# cpb-dslr-remote-shield.net
KiCad netlist of a schematic drawn in EAGLE
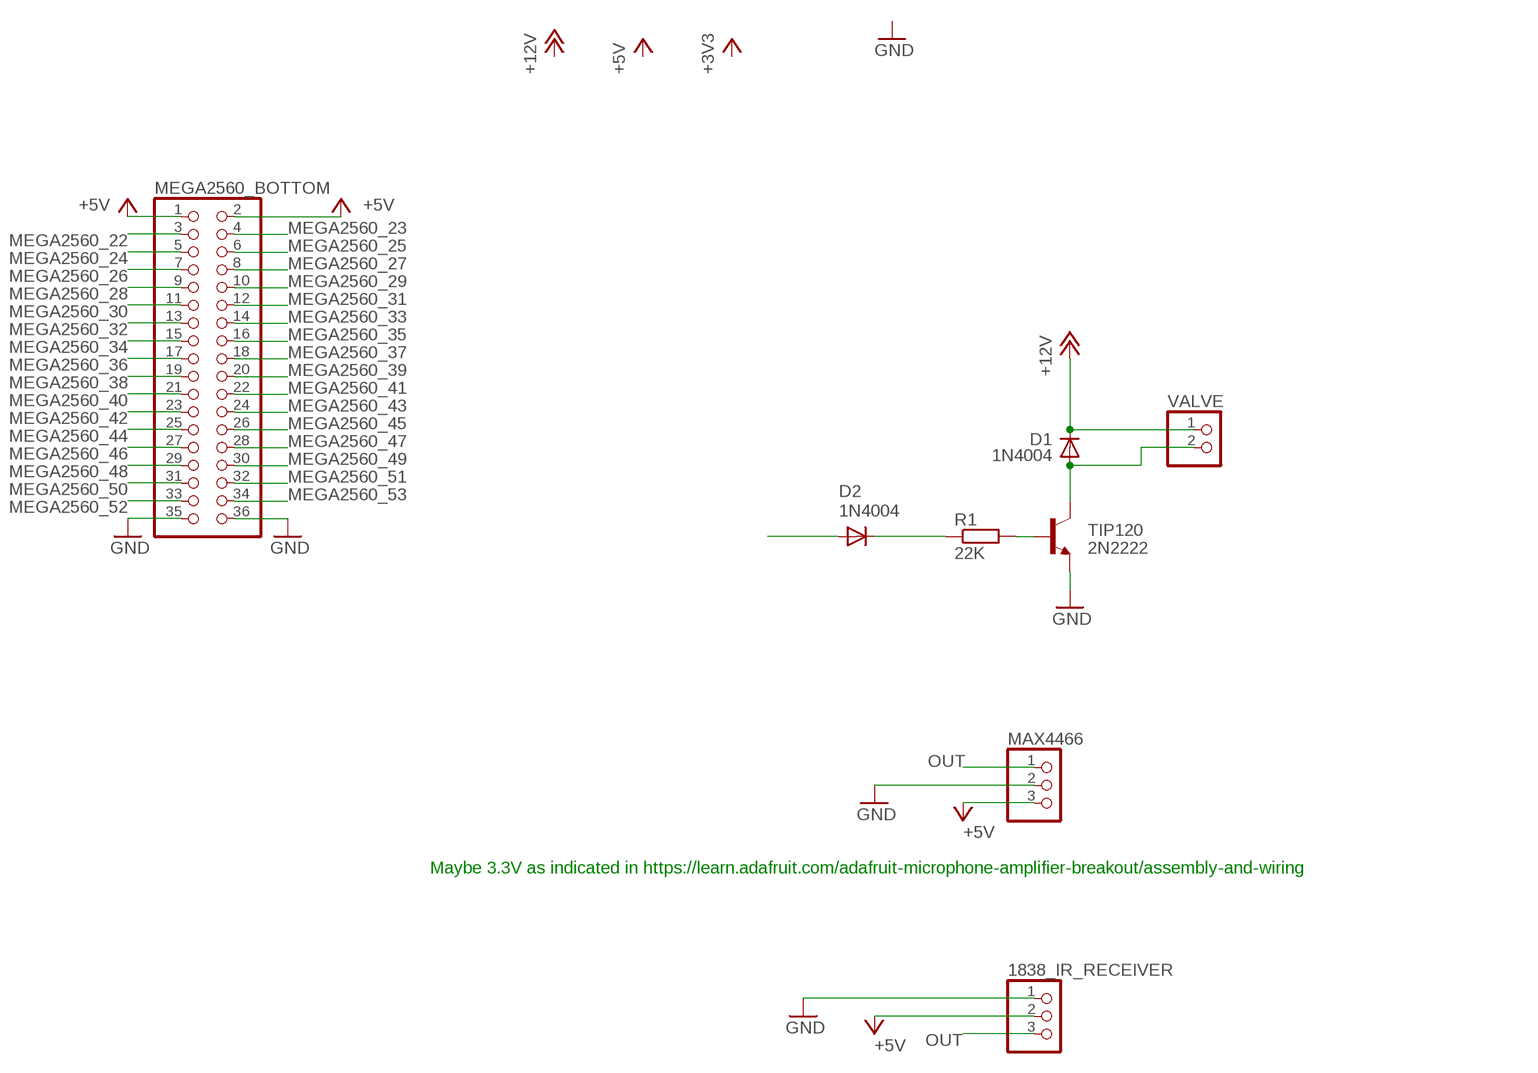
[diagram p0: schematic, sheet 1]

(export (version "E")
  (design (tool "Eeschema 10.0.6"))
  (components
    (comp (ref "1838_IR_RECEIVER")
      (value "PINHD-1X3")
      (footprint "eagle-import:1X03")
      (libsource (lib "eagle-import") (part "PINHD-1X3"))
    )
    (comp (ref "D1")
      (value "1N4004")
      (footprint "eagle-import:DO41-10")
      (libsource (lib "eagle-import") (part "1N4004"))
    )
    (comp (ref "D2")
      (value "1N4004")
      (footprint "eagle-import:DO41-10")
      (libsource (lib "eagle-import") (part "1N4004"))
    )
    (comp (ref "MAX4466")
      (value "PINHD-1X3")
      (footprint "eagle-import:1X03")
      (libsource (lib "eagle-import") (part "PINHD-1X3"))
    )
    (comp (ref "MEGA2560_BOTTOM")
      (value "PINHD-2X18")
      (footprint "eagle-import:2X18")
      (libsource (lib "eagle-import") (part "PINHD-2X18"))
    )
    (comp (ref "R1")
      (value "22K")
      (footprint "eagle-import:R0603")
      (libsource (lib "eagle-import") (part "R-EU_R0603"))
    )
    (comp (ref "TIP120")
      (value "2N2222")
      (footprint "eagle-import:TO92-EBC-OVAL")
      (libsource (lib "eagle-import") (part "2N2222"))
    )
    (comp (ref "VALVE")
      (value "PINHD-1X2")
      (footprint "eagle-import:1X02")
      (libsource (lib "eagle-import") (part "PINHD-1X2"))
    )
  )
  (nets
    (net (code "2") (name "+5V") (class "Default")
      (node (ref "1838_IR_RECEIVER") (pin "2") (pinfunction "2_2") (pintype "passive"))
      (node (ref "MAX4466") (pin "3") (pinfunction "3_3") (pintype "passive"))
      (node (ref "MEGA2560_BOTTOM") (pin "1") (pinfunction "1_1") (pintype "passive"))
      (node (ref "MEGA2560_BOTTOM") (pin "2") (pinfunction "2_2") (pintype "passive"))
    )
    (net (code "3") (name "+12V") (class "Default")
      (node (ref "D1") (pin "C") (pinfunction "C_C") (pintype "passive"))
      (node (ref "VALVE") (pin "1") (pinfunction "1_1") (pintype "passive"))
    )
    (net (code "4") (name "/MEGA2560_22") (class "Default")
      (node (ref "MEGA2560_BOTTOM") (pin "3") (pinfunction "3_3") (pintype "passive"))
    )
    (net (code "5") (name "/MEGA2560_23") (class "Default")
      (node (ref "MEGA2560_BOTTOM") (pin "4") (pinfunction "4_4") (pintype "passive"))
    )
    (net (code "6") (name "/MEGA2560_24") (class "Default")
      (node (ref "MEGA2560_BOTTOM") (pin "5") (pinfunction "5_5") (pintype "passive"))
    )
    (net (code "7") (name "/MEGA2560_25") (class "Default")
      (node (ref "MEGA2560_BOTTOM") (pin "6") (pinfunction "6_6") (pintype "passive"))
    )
    (net (code "8") (name "/MEGA2560_26") (class "Default")
      (node (ref "MEGA2560_BOTTOM") (pin "7") (pinfunction "7_7") (pintype "passive"))
    )
    (net (code "9") (name "/MEGA2560_27") (class "Default")
      (node (ref "MEGA2560_BOTTOM") (pin "8") (pinfunction "8_8") (pintype "passive"))
    )
    (net (code "10") (name "/MEGA2560_28") (class "Default")
      (node (ref "MEGA2560_BOTTOM") (pin "9") (pinfunction "9_9") (pintype "passive"))
    )
    (net (code "11") (name "/MEGA2560_29") (class "Default")
      (node (ref "MEGA2560_BOTTOM") (pin "10") (pinfunction "10_10") (pintype "passive"))
    )
    (net (code "12") (name "/MEGA2560_30") (class "Default")
      (node (ref "MEGA2560_BOTTOM") (pin "11") (pinfunction "11_11") (pintype "passive"))
    )
    (net (code "13") (name "/MEGA2560_31") (class "Default")
      (node (ref "MEGA2560_BOTTOM") (pin "12") (pinfunction "12_12") (pintype "passive"))
    )
    (net (code "14") (name "/MEGA2560_32") (class "Default")
      (node (ref "MEGA2560_BOTTOM") (pin "13") (pinfunction "13_13") (pintype "passive"))
    )
    (net (code "15") (name "/MEGA2560_33") (class "Default")
      (node (ref "MEGA2560_BOTTOM") (pin "14") (pinfunction "14_14") (pintype "passive"))
    )
    (net (code "16") (name "/MEGA2560_34") (class "Default")
      (node (ref "MEGA2560_BOTTOM") (pin "15") (pinfunction "15_15") (pintype "passive"))
    )
    (net (code "17") (name "/MEGA2560_35") (class "Default")
      (node (ref "MEGA2560_BOTTOM") (pin "16") (pinfunction "16_16") (pintype "passive"))
    )
    (net (code "18") (name "/MEGA2560_36") (class "Default")
      (node (ref "MEGA2560_BOTTOM") (pin "17") (pinfunction "17_17") (pintype "passive"))
    )
    (net (code "19") (name "/MEGA2560_37") (class "Default")
      (node (ref "MEGA2560_BOTTOM") (pin "18") (pinfunction "18_18") (pintype "passive"))
    )
    (net (code "20") (name "/MEGA2560_38") (class "Default")
      (node (ref "MEGA2560_BOTTOM") (pin "19") (pinfunction "19_19") (pintype "passive"))
    )
    (net (code "21") (name "/MEGA2560_39") (class "Default")
      (node (ref "MEGA2560_BOTTOM") (pin "20") (pinfunction "20_20") (pintype "passive"))
    )
    (net (code "22") (name "/MEGA2560_40") (class "Default")
      (node (ref "MEGA2560_BOTTOM") (pin "21") (pinfunction "21_21") (pintype "passive"))
    )
    (net (code "23") (name "/MEGA2560_41") (class "Default")
      (node (ref "MEGA2560_BOTTOM") (pin "22") (pinfunction "22_22") (pintype "passive"))
    )
    (net (code "24") (name "/MEGA2560_42") (class "Default")
      (node (ref "MEGA2560_BOTTOM") (pin "23") (pinfunction "23_23") (pintype "passive"))
    )
    (net (code "25") (name "/MEGA2560_43") (class "Default")
      (node (ref "MEGA2560_BOTTOM") (pin "24") (pinfunction "24_24") (pintype "passive"))
    )
    (net (code "26") (name "/MEGA2560_44") (class "Default")
      (node (ref "MEGA2560_BOTTOM") (pin "25") (pinfunction "25_25") (pintype "passive"))
    )
    (net (code "27") (name "/MEGA2560_45") (class "Default")
      (node (ref "MEGA2560_BOTTOM") (pin "26") (pinfunction "26_26") (pintype "passive"))
    )
    (net (code "28") (name "/MEGA2560_46") (class "Default")
      (node (ref "MEGA2560_BOTTOM") (pin "27") (pinfunction "27_27") (pintype "passive"))
    )
    (net (code "29") (name "/MEGA2560_47") (class "Default")
      (node (ref "MEGA2560_BOTTOM") (pin "28") (pinfunction "28_28") (pintype "passive"))
    )
    (net (code "30") (name "/MEGA2560_48") (class "Default")
      (node (ref "MEGA2560_BOTTOM") (pin "29") (pinfunction "29_29") (pintype "passive"))
    )
    (net (code "31") (name "/MEGA2560_49") (class "Default")
      (node (ref "MEGA2560_BOTTOM") (pin "30") (pinfunction "30_30") (pintype "passive"))
    )
    (net (code "32") (name "/MEGA2560_50") (class "Default")
      (node (ref "MEGA2560_BOTTOM") (pin "31") (pinfunction "31_31") (pintype "passive"))
    )
    (net (code "33") (name "/MEGA2560_51") (class "Default")
      (node (ref "MEGA2560_BOTTOM") (pin "32") (pinfunction "32_32") (pintype "passive"))
    )
    (net (code "34") (name "/MEGA2560_52") (class "Default")
      (node (ref "MEGA2560_BOTTOM") (pin "33") (pinfunction "33_33") (pintype "passive"))
    )
    (net (code "35") (name "/MEGA2560_53") (class "Default")
      (node (ref "MEGA2560_BOTTOM") (pin "34") (pinfunction "34_34") (pintype "passive"))
    )
    (net (code "36") (name "/OUT") (class "Default")
      (node (ref "1838_IR_RECEIVER") (pin "3") (pinfunction "3_3") (pintype "passive"))
      (node (ref "MAX4466") (pin "1") (pinfunction "1_1") (pintype "passive"))
    )
    (net (code "37") (name "GND") (class "Default")
      (node (ref "1838_IR_RECEIVER") (pin "1") (pinfunction "1_1") (pintype "passive"))
      (node (ref "MAX4466") (pin "2") (pinfunction "2_2") (pintype "passive"))
      (node (ref "MEGA2560_BOTTOM") (pin "35") (pinfunction "35_35") (pintype "passive"))
      (node (ref "MEGA2560_BOTTOM") (pin "36") (pinfunction "36_36") (pintype "passive"))
      (node (ref "TIP120") (pin "E") (pinfunction "E_E") (pintype "passive"))
    )
    (net (code "38") (name "Net-(D1-PadA)") (class "Default")
      (node (ref "D1") (pin "A") (pinfunction "A_A") (pintype "passive"))
      (node (ref "TIP120") (pin "C") (pinfunction "C_C") (pintype "passive"))
      (node (ref "VALVE") (pin "2") (pinfunction "2_2") (pintype "passive"))
    )
    (net (code "39") (name "Net-(D2-PadC)") (class "Default")
      (node (ref "D2") (pin "C") (pinfunction "C_C") (pintype "passive"))
      (node (ref "R1") (pin "1") (pinfunction "1_1") (pintype "passive"))
    )
    (net (code "40") (name "Net-(R1-Pad2)") (class "Default")
      (node (ref "R1") (pin "2") (pinfunction "2_2") (pintype "passive"))
      (node (ref "TIP120") (pin "B") (pinfunction "B_B") (pintype "passive"))
    )
    (net (code "41") (name "unconnected-(D2-PadA)") (class "Default")
      (node (ref "D2") (pin "A") (pinfunction "A_A") (pintype "passive"))
    )
  )
)
